# SCH_HackerCard_2025-04-15.net
KiCad netlist of a schematic drawn in EasyEDA
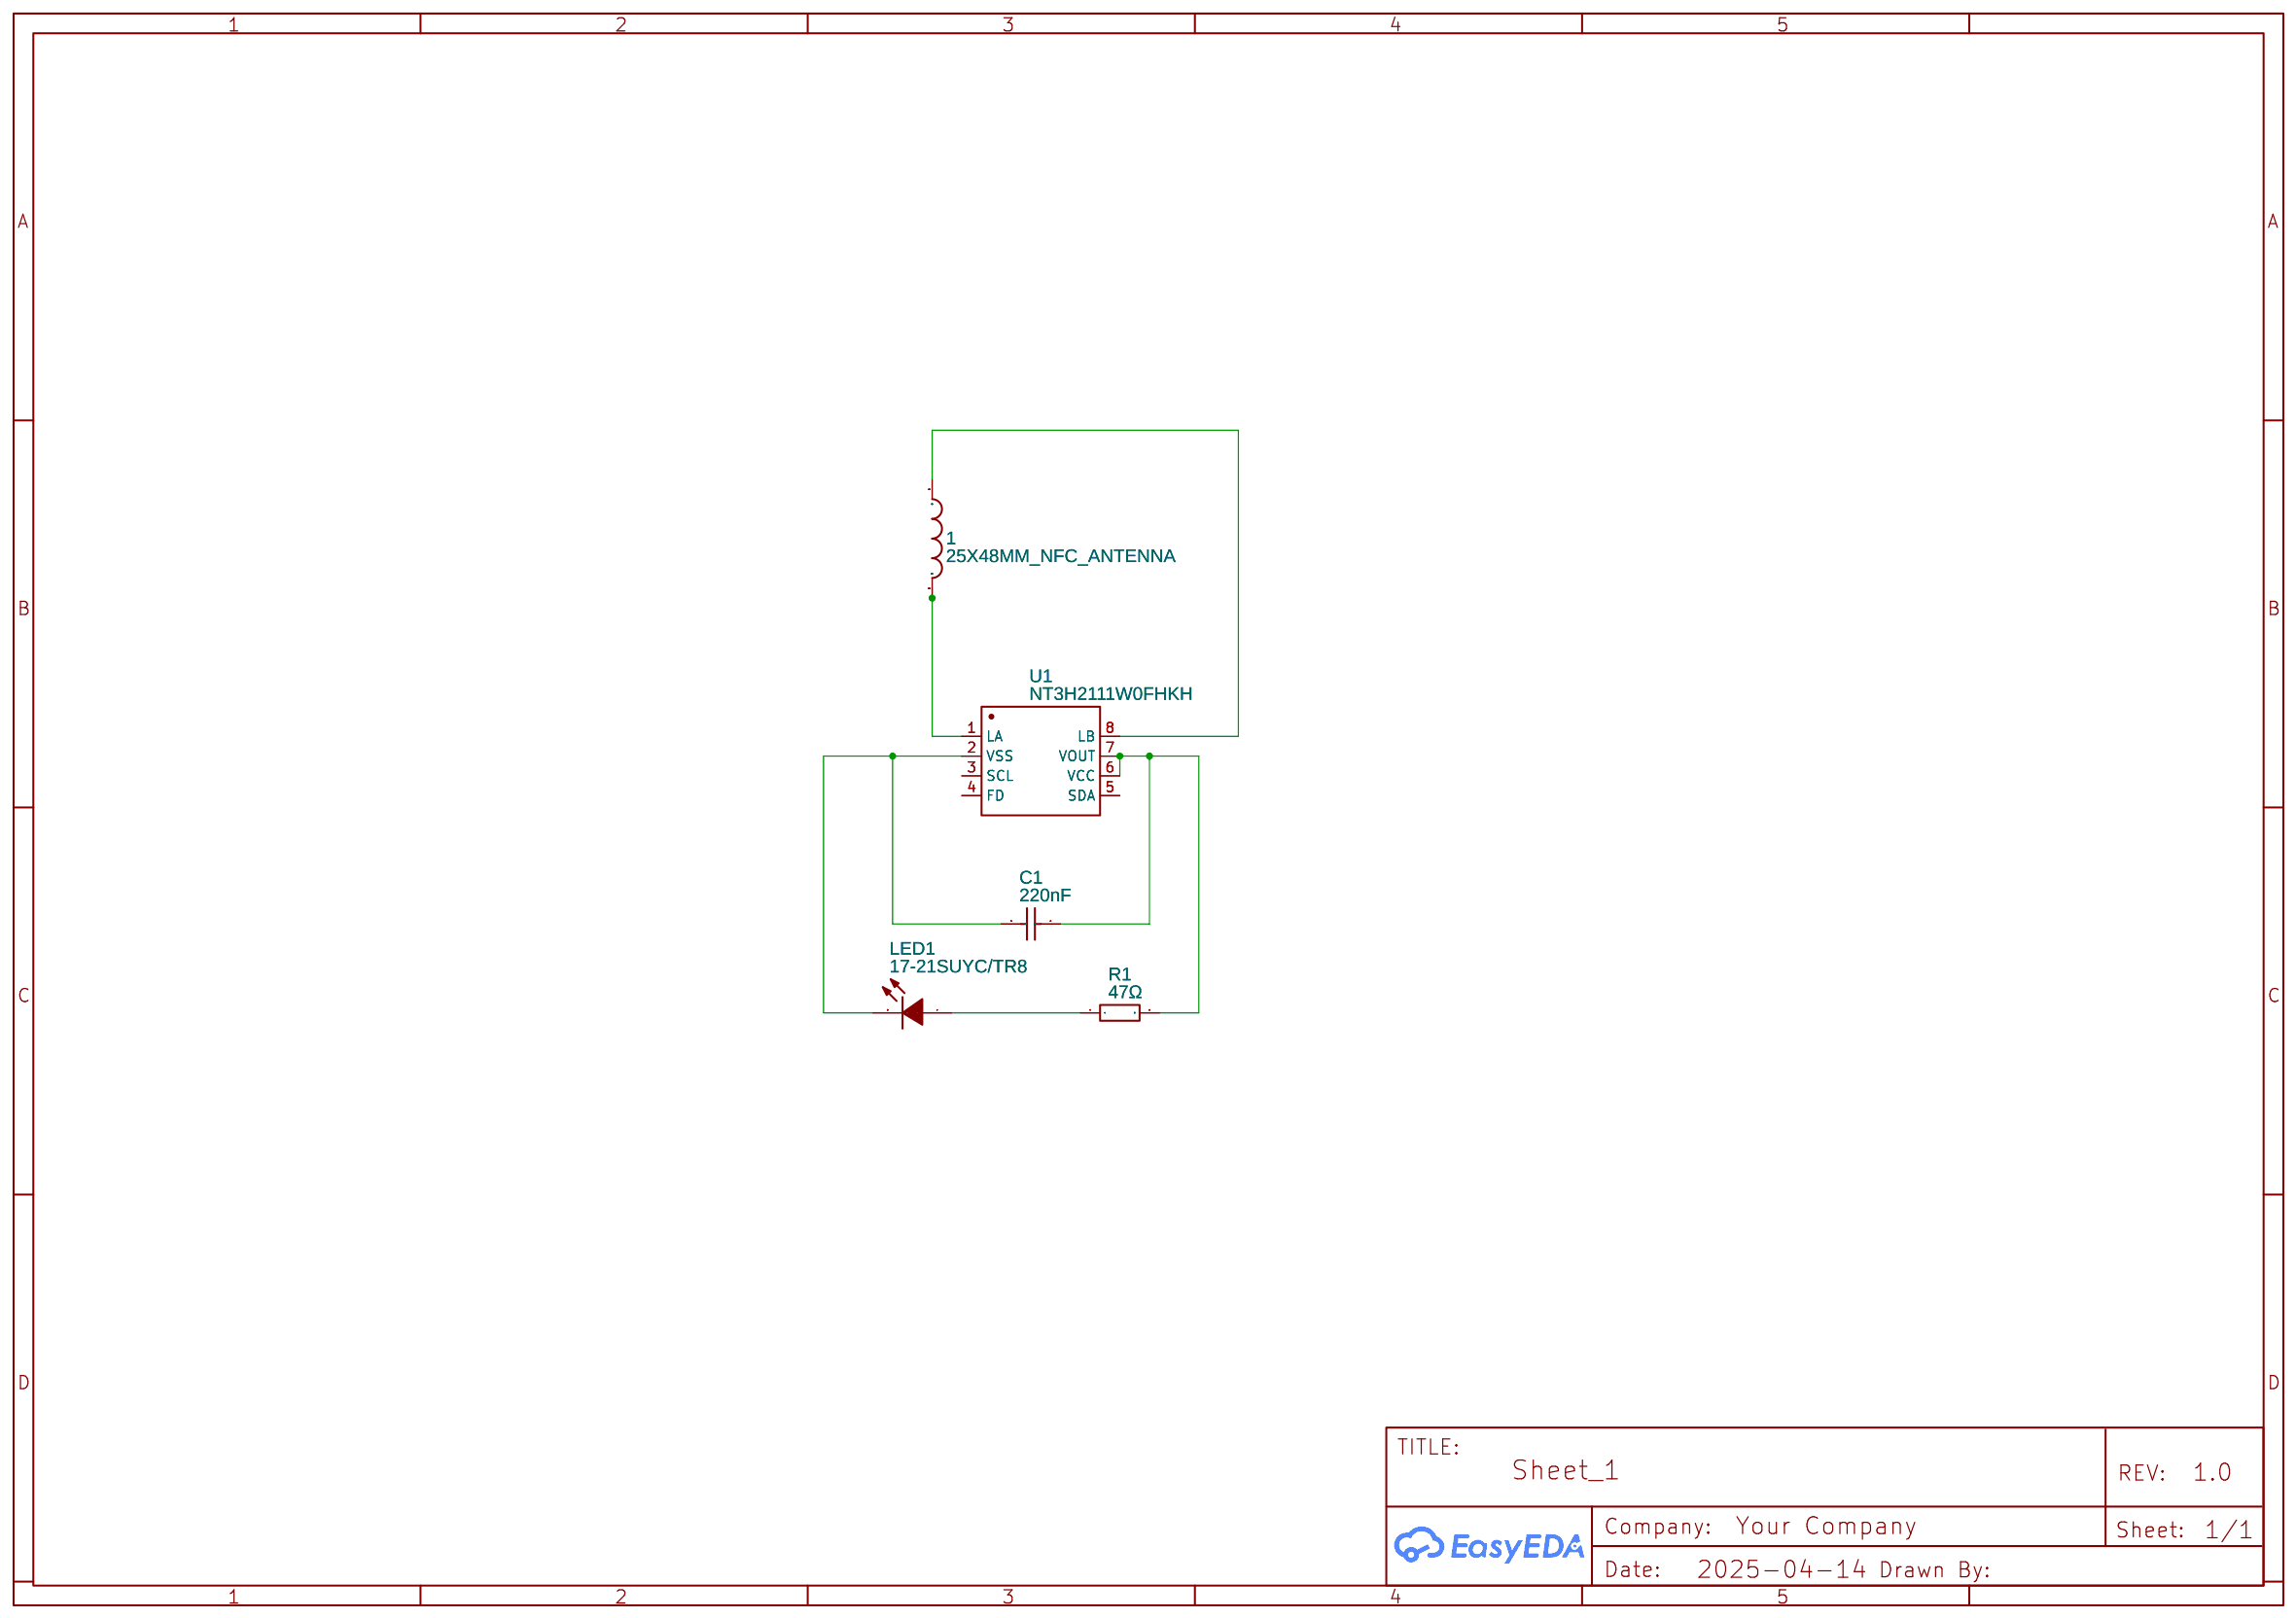
[diagram p0: schematic sheet]

(export (version "E")
  (design (tool "Eeschema 10.0.6"))
  (components
    (comp (ref "1") (value "25X48MM_NFC_ANTENNA") (libsource (lib "") (part "25X48MM_NFC_ANTENNA")))
    (comp (ref "C1")
      (value "220nF")
      (fields
        (field (name "Manufacturer Part") "CL10B224KA8NNNC")
        (field (name "Manufacturer") "SAMSUNG(三星)")
      )
      (libsource (lib "") (part "CL10B224KA8NNNC"))
    )
    (comp (ref "LED1")
      (value "17-21SUYC/TR8")
      (fields (field (name "Manufacturer Part") "KT-0805黄灯") (field (name "Manufacturer") "KENTO"))
      (libsource (lib "") (part "17-21SUYC/TR8"))
    )
    (comp (ref "R1")
      (value "47Ω")
      (fields
        (field (name "Manufacturer Part") "0603WAF470JT5E")
        (field (name "Manufacturer") "UNI-ROYAL(厚声)")
      )
      (libsource (lib "") (part "0603WAF470JT5E"))
    )
    (comp (ref "U1")
      (value "NT3H2111W0FHKH")
      (fields (field (name "Manufacturer") "NXP(恩智浦)"))
      (libsource (lib "") (part "NT3H2111W0FHKH"))
    )
  )
  (nets
    (net (code "1") (name "Net-(LED1-+)") (class "Default")
      (node (ref "LED1") (pin "1") (pinfunction "+_1") (pintype "unspecified"))
      (node (ref "R1") (pin "1") (pinfunction "1_1") (pintype "input"))
    )
    (net (code "2") (name "Net-(LED1--)") (class "Default")
      (node (ref "C1") (pin "1") (pinfunction "1_1") (pintype "input"))
      (node (ref "LED1") (pin "2") (pinfunction "-_2") (pintype "unspecified"))
      (node (ref "U1") (pin "2") (pinfunction "VSS_2") (pintype "unspecified"))
    )
    (net (code "3") (name "Net-(U1-LA)") (class "Default")
      (node (ref "1") (pin "P$2") (pinfunction "P$2_P$2") (pintype "bidirectional"))
      (node (ref "U1") (pin "1") (pinfunction "LA_1") (pintype "unspecified"))
    )
    (net (code "4") (name "Net-(U1-LB)") (class "Default")
      (node (ref "1") (pin "P$1") (pinfunction "P$1_P$1") (pintype "bidirectional"))
      (node (ref "U1") (pin "8") (pinfunction "LB_8") (pintype "unspecified"))
    )
    (net (code "5") (name "Net-(U1-VCC)") (class "Default")
      (node (ref "C1") (pin "2") (pinfunction "2_2") (pintype "input"))
      (node (ref "R1") (pin "2") (pinfunction "2_2") (pintype "input"))
      (node (ref "U1") (pin "6") (pinfunction "VCC_6") (pintype "unspecified"))
      (node (ref "U1") (pin "7") (pinfunction "VOUT_7") (pintype "unspecified"))
    )
    (net (code "6") (name "unconnected-(U1-FD-Pad4)") (class "Default")
      (node (ref "U1") (pin "4") (pinfunction "FD_4") (pintype "unspecified"))
    )
    (net (code "7") (name "unconnected-(U1-SCL-Pad3)") (class "Default")
      (node (ref "U1") (pin "3") (pinfunction "SCL_3") (pintype "unspecified"))
    )
    (net (code "8") (name "unconnected-(U1-SDA-Pad5)") (class "Default")
      (node (ref "U1") (pin "5") (pinfunction "SDA_5") (pintype "unspecified"))
    )
  )
)
